# logic.net
KiCad netlist of a schematic drawn in EAGLE
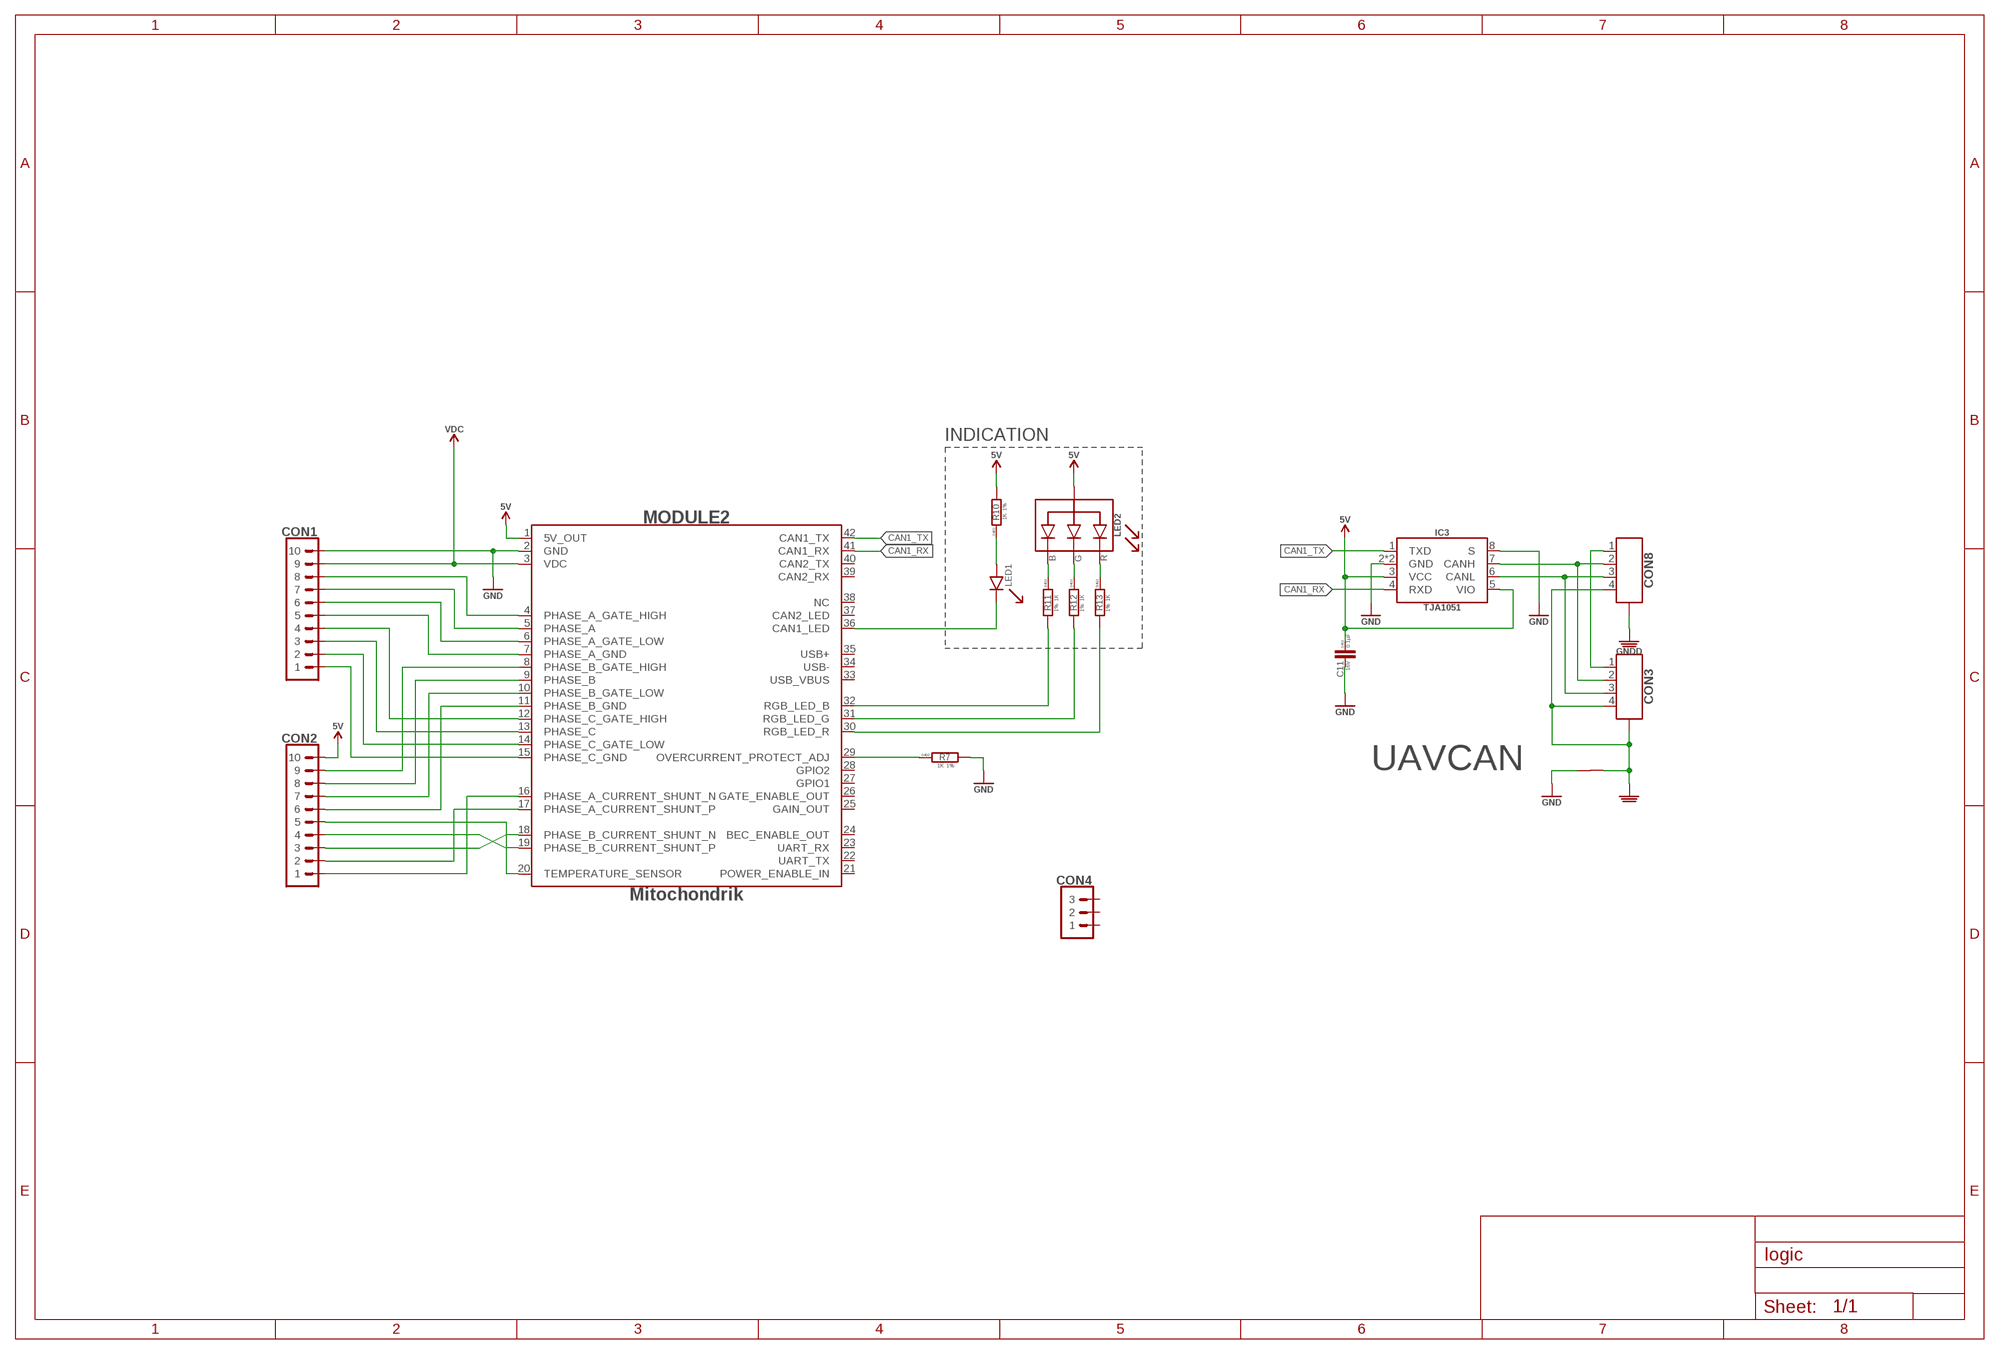
[diagram p0: schematic, sheet 1]

(export (version "E")
  (design (tool "Eeschema 10.0.6"))
  (components
    (comp (ref "C11")
      (value "0.1µF")
      (footprint "eagle-import:C0402")
      (fields
        (field (name "MANF") "Murata Electronics North America")
        (field (name "PACKAGE") "0402")
        (field (name "TOLERANCE") "+-10%")
        (field (name "VOLTAGE") "16V")
      )
      (libsource (lib "eagle-import") (part "0.1µF-0402-16V_10%_X7R"))
    )
    (comp (ref "CON1")
      (value "PINHEAD_1X10-2")
      (footprint "eagle-import:1X10-PTH_2")
      (libsource (lib "eagle-import") (part "PINHEAD_1X10-2"))
    )
    (comp (ref "CON2")
      (value "PINHEAD_1X10-2")
      (footprint "eagle-import:1X10-PTH_2")
      (libsource (lib "eagle-import") (part "PINHEAD_1X10-2"))
    )
    (comp (ref "CON3")
      (value "CON-4P-JST_GH-RA")
      (footprint "eagle-import:JST_GH-4P-RA")
      (fields (field (name "MANF") "JST Sales America Inc"))
      (libsource (lib "eagle-import") (part "CON-4P-RA-JST_GH"))
    )
    (comp (ref "CON4")
      (value "PINHEAD_1X03-2.54-RA")
      (footprint "eagle-import:1X03-PTH-2.54-RA")
      (libsource (lib "eagle-import") (part "PINHEAD_1X03-2.54-RA"))
    )
    (comp (ref "CON8")
      (value "CON-4P-JST_GH-RA")
      (footprint "eagle-import:JST_GH-4P-RA")
      (fields (field (name "MANF") "JST Sales America Inc"))
      (libsource (lib "eagle-import") (part "CON-4P-RA-JST_GH"))
    )
    (comp (ref "IC3")
      (value "TJA1051")
      (footprint "eagle-import:SOT782-1")
      (fields (field (name "MANF") "NXP Semiconductors"))
      (libsource (lib "eagle-import") (part "TJA1051"))
    )
    (comp (ref "LED1")
      (value "GREEN")
      (footprint "eagle-import:0402_LED")
      (fields (field (name "MANF") "Rohm Semiconductor"))
      (libsource (lib "eagle-import") (part "LED-0402-GREEN"))
    )
    (comp (ref "LED2")
      (value "LTST-C19HE1WT")
      (footprint "eagle-import:LITE_ON_RGB_LED")
      (fields (field (name "MANF") "Lite-On Inc"))
      (libsource (lib "eagle-import") (part "LTST-C19HE1WT"))
    )
    (comp (ref "MODULE2")
      (value "MITOHONDRIQUE-TH")
      (footprint "eagle-import:MITOHONDRIQUE")
      (fields (field (name "MANF#") "Mitochondrik") (field (name "MANF") "Zubax Robotics"))
      (libsource (lib "eagle-import") (part "MITOHONDRIQUE-TH"))
    )
    (comp (ref "R7")
      (value "1K")
      (footprint "eagle-import:R0402")
      (fields (field (name "MANF") "Yageo") (field (name "PACKAGE") "0402") (field (name "TOLERANCE") "1%"))
      (libsource (lib "eagle-import") (part "1K-0402-1%"))
    )
    (comp (ref "R10")
      (value "1K")
      (footprint "eagle-import:R0402")
      (fields (field (name "MANF") "Yageo") (field (name "PACKAGE") "0402") (field (name "TOLERANCE") "1%"))
      (libsource (lib "eagle-import") (part "1K-0402-1%"))
    )
    (comp (ref "R11")
      (value "1K")
      (footprint "eagle-import:R0402")
      (fields (field (name "MANF") "Yageo") (field (name "PACKAGE") "0402") (field (name "TOLERANCE") "1%"))
      (libsource (lib "eagle-import") (part "1K-0402-1%"))
    )
    (comp (ref "R12")
      (value "1K")
      (footprint "eagle-import:R0402")
      (fields (field (name "MANF") "Yageo") (field (name "PACKAGE") "0402") (field (name "TOLERANCE") "1%"))
      (libsource (lib "eagle-import") (part "1K-0402-1%"))
    )
    (comp (ref "R13")
      (value "1K")
      (footprint "eagle-import:R0402")
      (fields (field (name "MANF") "Yageo") (field (name "PACKAGE") "0402") (field (name "TOLERANCE") "1%"))
      (libsource (lib "eagle-import") (part "1K-0402-1%"))
    )
    (comp (ref "U$2")
      (value "CONNECTION")
      (footprint "eagle-import:CONNECTION")
      (libsource (lib "eagle-import") (part "CONNECTION"))
    )
  )
  (nets
    (net (code "1") (name "5V") (class "Default")
      (node (ref "C11") (pin "1") (pinfunction "1_1") (pintype "passive"))
      (node (ref "CON2") (pin "10") (pinfunction "10_10") (pintype "passive"))
      (node (ref "IC3") (pin "3") (pinfunction "VCC_3") (pintype "bidirectional"))
      (node (ref "IC3") (pin "5") (pinfunction "VIO_5") (pintype "bidirectional"))
      (node (ref "LED2") (pin "+") (pinfunction "A_+") (pintype "bidirectional"))
      (node (ref "MODULE2") (pin "1") (pinfunction "5V_OUT_1") (pintype "power_in"))
      (node (ref "R10") (pin "2") (pinfunction "2_2") (pintype "passive"))
    )
    (net (code "2") (name "CAN1_RX") (class "Default")
      (node (ref "IC3") (pin "4") (pinfunction "RXD_4") (pintype "bidirectional"))
      (node (ref "MODULE2") (pin "41") (pinfunction "CAN1_RX_41") (pintype "input"))
    )
    (net (code "3") (name "CAN1_TX") (class "Default")
      (node (ref "IC3") (pin "1") (pinfunction "TXD_1") (pintype "bidirectional"))
      (node (ref "MODULE2") (pin "42") (pinfunction "CAN1_TX_42") (pintype "output"))
    )
    (net (code "4") (name "GND") (class "Default")
      (node (ref "C11") (pin "2") (pinfunction "2_2") (pintype "passive"))
      (node (ref "CON1") (pin "10") (pinfunction "10_10") (pintype "passive"))
      (node (ref "IC3") (pin "2") (pinfunction "GND_2") (pintype "bidirectional"))
      (node (ref "IC3") (pin "8") (pinfunction "S_8") (pintype "bidirectional"))
      (node (ref "IC3") (pin "PAD") (pinfunction "GND_PAD") (pintype "bidirectional"))
      (node (ref "MODULE2") (pin "2") (pinfunction "GND_2") (pintype "power_in"))
      (node (ref "R7") (pin "2") (pinfunction "2_2") (pintype "passive"))
      (node (ref "U$2") (pin "P$1") (pinfunction "P$1_P$1") (pintype "bidirectional"))
    )
    (net (code "5") (name "GNDD") (class "Default")
      (node (ref "CON3") (pin "4") (pinfunction "4_4") (pintype "bidirectional"))
      (node (ref "CON3") (pin "M$0") (pinfunction "GND_M$0") (pintype "bidirectional"))
      (node (ref "CON3") (pin "M$1") (pinfunction "GND_M$1") (pintype "bidirectional"))
      (node (ref "CON8") (pin "4") (pinfunction "4_4") (pintype "bidirectional"))
      (node (ref "CON8") (pin "M$0") (pinfunction "GND_M$0") (pintype "bidirectional"))
      (node (ref "CON8") (pin "M$1") (pinfunction "GND_M$1") (pintype "bidirectional"))
      (node (ref "U$2") (pin "P$2") (pinfunction "P$2_P$2") (pintype "bidirectional"))
    )
    (net (code "6") (name "Net-(CON3-Pad1)") (class "Default")
      (node (ref "CON3") (pin "1") (pinfunction "1_1") (pintype "bidirectional"))
      (node (ref "CON8") (pin "1") (pinfunction "1_1") (pintype "bidirectional"))
    )
    (net (code "7") (name "Net-(IC3-CANH)") (class "Default")
      (node (ref "CON3") (pin "2") (pinfunction "2_2") (pintype "bidirectional"))
      (node (ref "CON8") (pin "2") (pinfunction "2_2") (pintype "bidirectional"))
      (node (ref "IC3") (pin "7") (pinfunction "CANH_7") (pintype "bidirectional"))
    )
    (net (code "8") (name "Net-(IC3-CANL)") (class "Default")
      (node (ref "CON3") (pin "3") (pinfunction "3_3") (pintype "bidirectional"))
      (node (ref "CON8") (pin "3") (pinfunction "3_3") (pintype "bidirectional"))
      (node (ref "IC3") (pin "6") (pinfunction "CANL_6") (pintype "bidirectional"))
    )
    (net (code "9") (name "Net-(LED1-PadA)") (class "Default")
      (node (ref "LED1") (pin "A") (pinfunction "A_A") (pintype "bidirectional"))
      (node (ref "R10") (pin "1") (pinfunction "1_1") (pintype "passive"))
    )
    (net (code "10") (name "Net-(LED2-PadB)") (class "Default")
      (node (ref "LED2") (pin "B") (pinfunction "B_B") (pintype "bidirectional"))
      (node (ref "R11") (pin "1") (pinfunction "1_1") (pintype "passive"))
    )
    (net (code "11") (name "Net-(LED2-PadG)") (class "Default")
      (node (ref "LED2") (pin "G") (pinfunction "G_G") (pintype "bidirectional"))
      (node (ref "R12") (pin "1") (pinfunction "1_1") (pintype "passive"))
    )
    (net (code "12") (name "Net-(LED2-PadR)") (class "Default")
      (node (ref "LED2") (pin "R") (pinfunction "R_R") (pintype "bidirectional"))
      (node (ref "R13") (pin "1") (pinfunction "1_1") (pintype "passive"))
    )
    (net (code "13") (name "Net-(MODULE2-CAN1_LED)") (class "Default")
      (node (ref "LED1") (pin "C") (pinfunction "C_C") (pintype "bidirectional"))
      (node (ref "MODULE2") (pin "36") (pinfunction "CAN1_LED_36") (pintype "output"))
    )
    (net (code "14") (name "Net-(MODULE2-OVERCURRENT_PROTECT_ADJ)") (class "Default")
      (node (ref "MODULE2") (pin "29") (pinfunction "OVERCURRENT_PROTECT_ADJ_29") (pintype "input"))
      (node (ref "R7") (pin "1") (pinfunction "1_1") (pintype "passive"))
    )
    (net (code "15") (name "Net-(MODULE2-PHASE_A)") (class "Default")
      (node (ref "CON1") (pin "7") (pinfunction "7_7") (pintype "passive"))
      (node (ref "MODULE2") (pin "5") (pinfunction "PHASE_A_5") (pintype "input"))
    )
    (net (code "16") (name "Net-(MODULE2-PHASE_A_CURRENT_SHUNT_N)") (class "Default")
      (node (ref "CON2") (pin "1") (pinfunction "1_1") (pintype "passive"))
      (node (ref "MODULE2") (pin "16") (pinfunction "PHASE_A_CURRENT_SHUNT_N_16") (pintype "input"))
    )
    (net (code "17") (name "Net-(MODULE2-PHASE_A_CURRENT_SHUNT_P)") (class "Default")
      (node (ref "CON2") (pin "2") (pinfunction "2_2") (pintype "passive"))
      (node (ref "MODULE2") (pin "17") (pinfunction "PHASE_A_CURRENT_SHUNT_P_17") (pintype "input"))
    )
    (net (code "18") (name "Net-(MODULE2-PHASE_A_GATE_HIGH)") (class "Default")
      (node (ref "CON1") (pin "8") (pinfunction "8_8") (pintype "passive"))
      (node (ref "MODULE2") (pin "4") (pinfunction "PHASE_A_GATE_HIGH_4") (pintype "output"))
    )
    (net (code "19") (name "Net-(MODULE2-PHASE_A_GATE_LOW)") (class "Default")
      (node (ref "CON1") (pin "6") (pinfunction "6_6") (pintype "passive"))
      (node (ref "MODULE2") (pin "6") (pinfunction "PHASE_A_GATE_LOW_6") (pintype "output"))
    )
    (net (code "20") (name "Net-(MODULE2-PHASE_A_GND)") (class "Default")
      (node (ref "CON1") (pin "5") (pinfunction "5_5") (pintype "passive"))
      (node (ref "MODULE2") (pin "7") (pinfunction "PHASE_A_GND_7") (pintype "input"))
    )
    (net (code "21") (name "Net-(MODULE2-PHASE_B)") (class "Default")
      (node (ref "CON2") (pin "8") (pinfunction "8_8") (pintype "passive"))
      (node (ref "MODULE2") (pin "9") (pinfunction "PHASE_B_9") (pintype "input"))
    )
    (net (code "22") (name "Net-(MODULE2-PHASE_B_CURRENT_SHUNT_N)") (class "Default")
      (node (ref "CON2") (pin "3") (pinfunction "3_3") (pintype "passive"))
      (node (ref "MODULE2") (pin "18") (pinfunction "PHASE_B_CURRENT_SHUNT_N_18") (pintype "input"))
    )
    (net (code "23") (name "Net-(MODULE2-PHASE_B_CURRENT_SHUNT_P)") (class "Default")
      (node (ref "CON2") (pin "4") (pinfunction "4_4") (pintype "passive"))
      (node (ref "MODULE2") (pin "19") (pinfunction "PHASE_B_CURRENT_SHUNT_P_19") (pintype "input"))
    )
    (net (code "24") (name "Net-(MODULE2-PHASE_B_GATE_HIGH)") (class "Default")
      (node (ref "CON2") (pin "9") (pinfunction "9_9") (pintype "passive"))
      (node (ref "MODULE2") (pin "8") (pinfunction "PHASE_B_GATE_HIGH_8") (pintype "output"))
    )
    (net (code "25") (name "Net-(MODULE2-PHASE_B_GATE_LOW)") (class "Default")
      (node (ref "CON2") (pin "7") (pinfunction "7_7") (pintype "passive"))
      (node (ref "MODULE2") (pin "10") (pinfunction "PHASE_B_GATE_LOW_10") (pintype "output"))
    )
    (net (code "26") (name "Net-(MODULE2-PHASE_B_GND)") (class "Default")
      (node (ref "CON2") (pin "6") (pinfunction "6_6") (pintype "passive"))
      (node (ref "MODULE2") (pin "11") (pinfunction "PHASE_B_GND_11") (pintype "input"))
    )
    (net (code "27") (name "Net-(MODULE2-PHASE_C)") (class "Default")
      (node (ref "CON1") (pin "3") (pinfunction "3_3") (pintype "passive"))
      (node (ref "MODULE2") (pin "13") (pinfunction "PHASE_C_13") (pintype "input"))
    )
    (net (code "28") (name "Net-(MODULE2-PHASE_C_GATE_HIGH)") (class "Default")
      (node (ref "CON1") (pin "4") (pinfunction "4_4") (pintype "passive"))
      (node (ref "MODULE2") (pin "12") (pinfunction "PHASE_C_GATE_HIGH_12") (pintype "output"))
    )
    (net (code "29") (name "Net-(MODULE2-PHASE_C_GATE_LOW)") (class "Default")
      (node (ref "CON1") (pin "2") (pinfunction "2_2") (pintype "passive"))
      (node (ref "MODULE2") (pin "14") (pinfunction "PHASE_C_GATE_LOW_14") (pintype "output"))
    )
    (net (code "30") (name "Net-(MODULE2-PHASE_C_GND)") (class "Default")
      (node (ref "CON1") (pin "1") (pinfunction "1_1") (pintype "passive"))
      (node (ref "MODULE2") (pin "15") (pinfunction "PHASE_C_GND_15") (pintype "input"))
    )
    (net (code "31") (name "Net-(MODULE2-RGB_LED_B)") (class "Default")
      (node (ref "MODULE2") (pin "32") (pinfunction "RGB_LED_B_32") (pintype "output"))
      (node (ref "R11") (pin "2") (pinfunction "2_2") (pintype "passive"))
    )
    (net (code "32") (name "Net-(MODULE2-RGB_LED_G)") (class "Default")
      (node (ref "MODULE2") (pin "31") (pinfunction "RGB_LED_G_31") (pintype "output"))
      (node (ref "R12") (pin "2") (pinfunction "2_2") (pintype "passive"))
    )
    (net (code "33") (name "Net-(MODULE2-RGB_LED_R)") (class "Default")
      (node (ref "MODULE2") (pin "30") (pinfunction "RGB_LED_R_30") (pintype "output"))
      (node (ref "R13") (pin "2") (pinfunction "2_2") (pintype "passive"))
    )
    (net (code "34") (name "Net-(MODULE2-TEMPERATURE_SENSOR)") (class "Default")
      (node (ref "CON2") (pin "5") (pinfunction "5_5") (pintype "passive"))
      (node (ref "MODULE2") (pin "20") (pinfunction "TEMPERATURE_SENSOR_20") (pintype "input"))
    )
    (net (code "35") (name "VDC") (class "Default")
      (node (ref "CON1") (pin "9") (pinfunction "9_9") (pintype "passive"))
      (node (ref "MODULE2") (pin "3") (pinfunction "VDC_3") (pintype "power_in"))
    )
    (net (code "36") (name "unconnected-(CON4-Pad1)") (class "Default")
      (node (ref "CON4") (pin "1") (pinfunction "1_1") (pintype "passive"))
    )
    (net (code "37") (name "unconnected-(CON4-Pad2)") (class "Default")
      (node (ref "CON4") (pin "2") (pinfunction "2_2") (pintype "passive"))
    )
    (net (code "38") (name "unconnected-(CON4-Pad3)") (class "Default")
      (node (ref "CON4") (pin "3") (pinfunction "3_3") (pintype "passive"))
    )
    (net (code "39") (name "unconnected-(MODULE2-BEC_ENABLE_OUT-Pad24)") (class "Default")
      (node (ref "MODULE2") (pin "24") (pinfunction "BEC_ENABLE_OUT_24") (pintype "output"))
    )
    (net (code "40") (name "unconnected-(MODULE2-CAN2_LED-Pad37)") (class "Default")
      (node (ref "MODULE2") (pin "37") (pinfunction "CAN2_LED_37") (pintype "output"))
    )
    (net (code "41") (name "unconnected-(MODULE2-CAN2_RX-Pad39)") (class "Default")
      (node (ref "MODULE2") (pin "39") (pinfunction "CAN2_RX_39") (pintype "input"))
    )
    (net (code "42") (name "unconnected-(MODULE2-CAN2_TX-Pad40)") (class "Default")
      (node (ref "MODULE2") (pin "40") (pinfunction "CAN2_TX_40") (pintype "output"))
    )
    (net (code "43") (name "unconnected-(MODULE2-GAIN_OUT-Pad25)") (class "Default")
      (node (ref "MODULE2") (pin "25") (pinfunction "GAIN_OUT_25") (pintype "output"))
    )
    (net (code "44") (name "unconnected-(MODULE2-GATE_ENABLE_OUT-Pad26)") (class "Default")
      (node (ref "MODULE2") (pin "26") (pinfunction "GATE_ENABLE_OUT_26") (pintype "output"))
    )
    (net (code "45") (name "unconnected-(MODULE2-GPIO1-Pad27)") (class "Default")
      (node (ref "MODULE2") (pin "27") (pinfunction "GPIO1_27") (pintype "bidirectional"))
    )
    (net (code "46") (name "unconnected-(MODULE2-GPIO2-Pad28)") (class "Default")
      (node (ref "MODULE2") (pin "28") (pinfunction "GPIO2_28") (pintype "bidirectional"))
    )
    (net (code "47") (name "unconnected-(MODULE2-NC-Pad38)") (class "Default")
      (node (ref "MODULE2") (pin "38") (pinfunction "NC_38") (pintype "no_connect"))
    )
    (net (code "48") (name "unconnected-(MODULE2-POWER_ENABLE_IN-Pad21)") (class "Default")
      (node (ref "MODULE2") (pin "21") (pinfunction "POWER_ENABLE_IN_21") (pintype "input"))
    )
    (net (code "49") (name "unconnected-(MODULE2-UART_RX-Pad23)") (class "Default")
      (node (ref "MODULE2") (pin "23") (pinfunction "UART_RX_23") (pintype "input"))
    )
    (net (code "50") (name "unconnected-(MODULE2-UART_TX-Pad22)") (class "Default")
      (node (ref "MODULE2") (pin "22") (pinfunction "UART_TX_22") (pintype "output"))
    )
    (net (code "51") (name "unconnected-(MODULE2-USB+-Pad35)") (class "Default")
      (node (ref "MODULE2") (pin "35") (pinfunction "USB+_35") (pintype "bidirectional"))
    )
    (net (code "52") (name "unconnected-(MODULE2-USB--Pad34)") (class "Default")
      (node (ref "MODULE2") (pin "34") (pinfunction "USB-_34") (pintype "bidirectional"))
    )
    (net (code "53") (name "unconnected-(MODULE2-USB_VBUS-Pad33)") (class "Default")
      (node (ref "MODULE2") (pin "33") (pinfunction "USB_VBUS_33") (pintype "input"))
    )
  )
)
